# RomeBoardV1.net
KiCad netlist of a schematic drawn in EAGLE
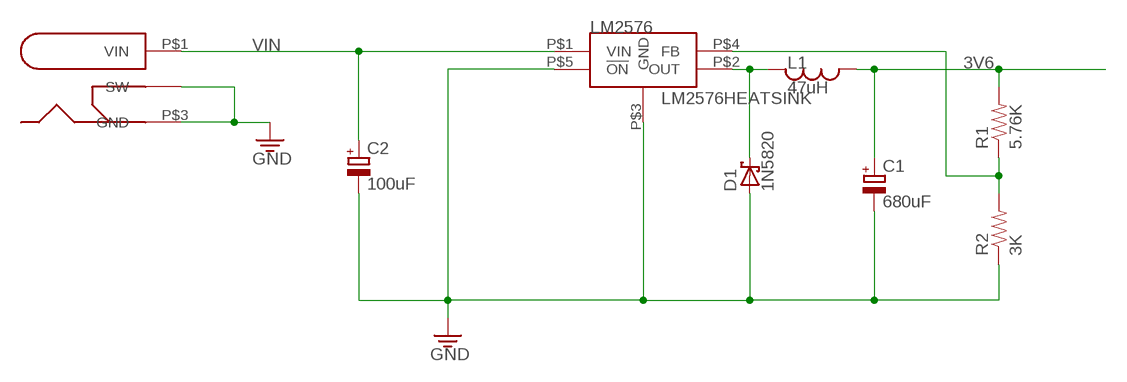
[diagram p0: schematic, sheet 1]
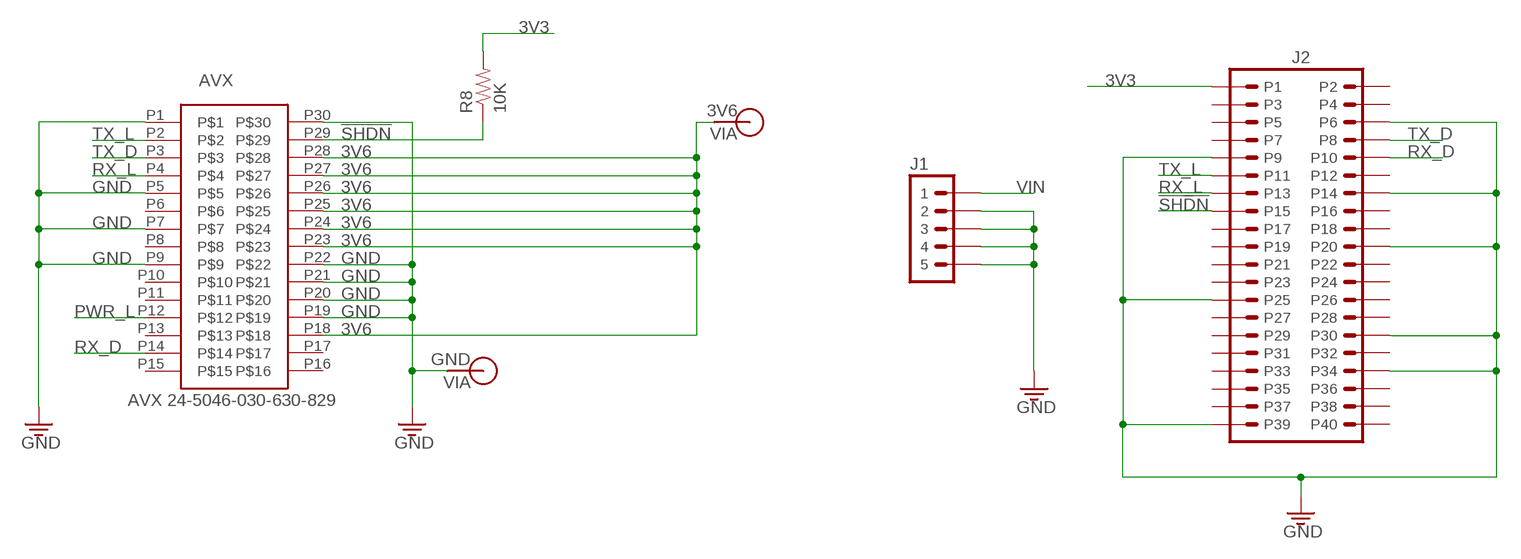
[diagram p1: schematic, sheet 2]
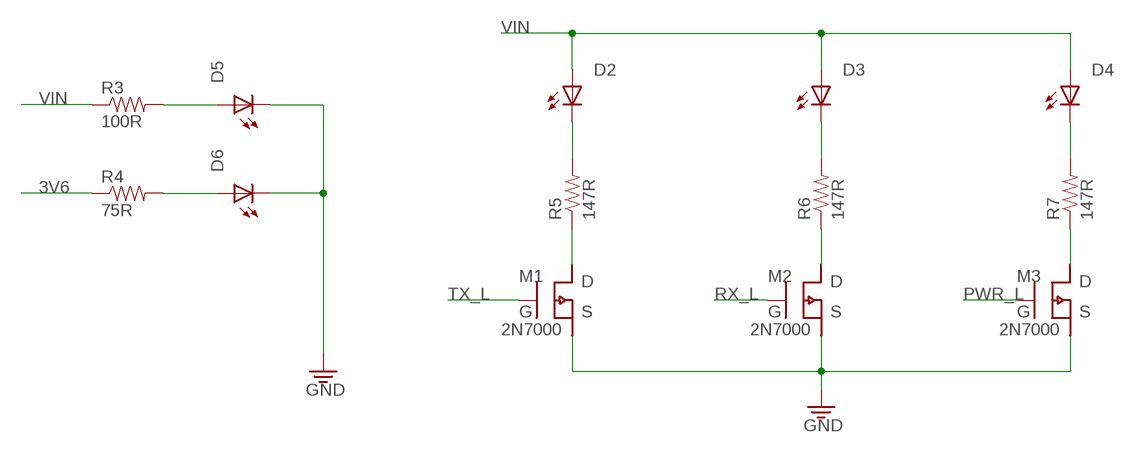
[diagram p2: schematic, sheet 3]

(export (version "E")
  (design (tool "Eeschema 10.0.6"))
  (components
    (comp (ref "AVX")
      (value "AVX-24-5046-030-630-829")
      (footprint "eagle-import:AVX-24-5046-630-829")
      (libsource (lib "eagle-import") (part "AVX-24-5046-030-630-829"))
    )
    (comp (ref "J1")
      (value "HEADER-5")
      (footprint "eagle-import:HEADER-05")
      (libsource (lib "eagle-import") (part "HEADER-5"))
    )
    (comp (ref "J2")
      (value "RASPBERRY-PI-HEADER")
      (footprint "eagle-import:HEADER-20X02")
      (libsource (lib "eagle-import") (part "RASPBERRY-PI-HEADER"))
    )
    (comp (ref "R8")
      (value "10K")
      (footprint "eagle-import:AXIAL-0.4")
      (libsource (lib "eagle-import") (part "RESISTOR-PTH0.4"))
    )
    (comp (ref "V4")
      (value "GND")
      (footprint "eagle-import:VIA-120MIL")
      (libsource (lib "eagle-import") (part "VIA-120MIL"))
    )
    (comp (ref "V5")
      (value "3V6")
      (footprint "eagle-import:VIA-120MIL")
      (libsource (lib "eagle-import") (part "VIA-120MIL"))
    )
    (comp (ref "C1")
      (value "680uF")
      (footprint "eagle-import:E5-10,5")
      (libsource (lib "eagle-import") (part "CPOL-EUE5-10.5"))
    )
    (comp (ref "C2")
      (value "100uF")
      (footprint "eagle-import:E3,5-10")
      (libsource (lib "eagle-import") (part "CPOL-EUE3.5-10"))
    )
    (comp (ref "D1")
      (value "1N5820")
      (footprint "eagle-import:DO-201AD")
      (libsource (lib "eagle-import") (part "1N5820"))
    )
    (comp (ref "L1")
      (value "47uH")
      (footprint "eagle-import:PE-53112NL")
      (libsource (lib "eagle-import") (part "INDPE-53112NL"))
    )
    (comp (ref "LM2576")
      (value "LM2576HEATSINK")
      (footprint "eagle-import:TO-220-5-HEATSINK")
      (libsource (lib "eagle-import") (part "LM2576HEATSINK"))
    )
    (comp (ref "R1")
      (value "5.76K")
      (footprint "eagle-import:AXIAL-0.4")
      (libsource (lib "eagle-import") (part "RESISTOR-PTH0.4"))
    )
    (comp (ref "R2")
      (value "3K")
      (footprint "eagle-import:AXIAL-0.4")
      (libsource (lib "eagle-import") (part "RESISTOR-PTH0.4"))
    )
    (comp (ref "U$2")
      (value "PJ-002A")
      (footprint "eagle-import:PJ-002A")
      (libsource (lib "eagle-import") (part "PJ-002A"))
    )
    (comp (ref "D2")
      (value "LEDTHRU-HOLE-CONNECTOR")
      (footprint "eagle-import:1X2-POL")
      (libsource (lib "eagle-import") (part "LEDTHRU-HOLE-CONNECTOR"))
    )
    (comp (ref "D3")
      (value "LEDTHRU-HOLE-CONNECTOR")
      (footprint "eagle-import:1X2-POL")
      (libsource (lib "eagle-import") (part "LEDTHRU-HOLE-CONNECTOR"))
    )
    (comp (ref "D4")
      (value "LEDTHRU-HOLE-CONNECTOR")
      (footprint "eagle-import:1X2-POL")
      (libsource (lib "eagle-import") (part "LEDTHRU-HOLE-CONNECTOR"))
    )
    (comp (ref "D5")
      (value "LEDTHRU-HOLE-CONNECTOR")
      (footprint "eagle-import:1X2-POL")
      (libsource (lib "eagle-import") (part "LEDTHRU-HOLE-CONNECTOR"))
    )
    (comp (ref "D6")
      (value "LEDTHRU-HOLE-CONNECTOR")
      (footprint "eagle-import:1X2-POL")
      (libsource (lib "eagle-import") (part "LEDTHRU-HOLE-CONNECTOR"))
    )
    (comp (ref "M1")
      (value "2N7000")
      (footprint "eagle-import:TO-923-MOS")
      (libsource (lib "eagle-import") (part "2N7000"))
    )
    (comp (ref "M2")
      (value "2N7000")
      (footprint "eagle-import:TO-923-MOS")
      (libsource (lib "eagle-import") (part "2N7000"))
    )
    (comp (ref "M3")
      (value "2N7000")
      (footprint "eagle-import:TO-923-MOS")
      (libsource (lib "eagle-import") (part "2N7000"))
    )
    (comp (ref "R3")
      (value "100R")
      (footprint "eagle-import:AXIAL-0.4")
      (libsource (lib "eagle-import") (part "RESISTOR-PTH0.4"))
    )
    (comp (ref "R4")
      (value "75R")
      (footprint "eagle-import:AXIAL-0.4")
      (libsource (lib "eagle-import") (part "RESISTOR-PTH0.4"))
    )
    (comp (ref "R5")
      (value "147R")
      (footprint "eagle-import:AXIAL-0.4")
      (libsource (lib "eagle-import") (part "RESISTOR-PTH0.4"))
    )
    (comp (ref "R6")
      (value "147R")
      (footprint "eagle-import:AXIAL-0.4")
      (libsource (lib "eagle-import") (part "RESISTOR-PTH0.4"))
    )
    (comp (ref "R7")
      (value "147R")
      (footprint "eagle-import:AXIAL-0.4")
      (libsource (lib "eagle-import") (part "RESISTOR-PTH0.4"))
    )
  )
  (nets
    (net (code "1") (name "3V3") (class "Default")
      (node (ref "J2") (pin "P1") (pinfunction "P1_P1") (pintype "passive"))
      (node (ref "R8") (pin "2") (pinfunction "2_2") (pintype "passive"))
    )
    (net (code "2") (name "3V6") (class "Default")
      (node (ref "AVX") (pin "P18") (pinfunction "P$18_P18") (pintype "bidirectional"))
      (node (ref "AVX") (pin "P23") (pinfunction "P$23_P23") (pintype "bidirectional"))
      (node (ref "AVX") (pin "P24") (pinfunction "P$24_P24") (pintype "bidirectional"))
      (node (ref "AVX") (pin "P25") (pinfunction "P$25_P25") (pintype "bidirectional"))
      (node (ref "AVX") (pin "P26") (pinfunction "P$26_P26") (pintype "bidirectional"))
      (node (ref "AVX") (pin "P27") (pinfunction "P$27_P27") (pintype "bidirectional"))
      (node (ref "AVX") (pin "P28") (pinfunction "P$28_P28") (pintype "bidirectional"))
      (node (ref "C1") (pin "+") (pinfunction "+_+") (pintype "passive"))
      (node (ref "L1") (pin "P$2") (pinfunction "P$2_P$2") (pintype "passive"))
      (node (ref "R1") (pin "2") (pinfunction "2_2") (pintype "passive"))
      (node (ref "R4") (pin "1") (pinfunction "1_1") (pintype "passive"))
      (node (ref "V5") (pin "P$1") (pinfunction "P$1_P$1") (pintype "bidirectional"))
    )
    (net (code "3") (name "GND") (class "Default")
      (node (ref "AVX") (pin "P1") (pinfunction "P$1_P1") (pintype "bidirectional"))
      (node (ref "AVX") (pin "P19") (pinfunction "P$19_P19") (pintype "bidirectional"))
      (node (ref "AVX") (pin "P20") (pinfunction "P$20_P20") (pintype "bidirectional"))
      (node (ref "AVX") (pin "P21") (pinfunction "P$21_P21") (pintype "bidirectional"))
      (node (ref "AVX") (pin "P22") (pinfunction "P$22_P22") (pintype "bidirectional"))
      (node (ref "AVX") (pin "P30") (pinfunction "P$30_P30") (pintype "bidirectional"))
      (node (ref "AVX") (pin "P5") (pinfunction "P$5_P5") (pintype "bidirectional"))
      (node (ref "AVX") (pin "P7") (pinfunction "P$7_P7") (pintype "bidirectional"))
      (node (ref "AVX") (pin "P9") (pinfunction "P$9_P9") (pintype "bidirectional"))
      (node (ref "C1") (pin "-") (pinfunction "-_-") (pintype "passive"))
      (node (ref "C2") (pin "-") (pinfunction "-_-") (pintype "passive"))
      (node (ref "D1") (pin "P$1") (pinfunction "A_P$1") (pintype "passive"))
      (node (ref "D5") (pin "2") (pinfunction "C_2") (pintype "passive"))
      (node (ref "D6") (pin "2") (pinfunction "C_2") (pintype "passive"))
      (node (ref "J1") (pin "2") (pinfunction "2_2") (pintype "passive"))
      (node (ref "J1") (pin "3") (pinfunction "3_3") (pintype "passive"))
      (node (ref "J1") (pin "4") (pinfunction "4_4") (pintype "passive"))
      (node (ref "J1") (pin "5") (pinfunction "5_5") (pintype "passive"))
      (node (ref "J2") (pin "P14") (pinfunction "P14_P14") (pintype "passive"))
      (node (ref "J2") (pin "P20") (pinfunction "P20_P20") (pintype "passive"))
      (node (ref "J2") (pin "P25") (pinfunction "P25_P25") (pintype "passive"))
      (node (ref "J2") (pin "P30") (pinfunction "P30_P30") (pintype "passive"))
      (node (ref "J2") (pin "P34") (pinfunction "P34_P34") (pintype "passive"))
      (node (ref "J2") (pin "P39") (pinfunction "P39_P39") (pintype "passive"))
      (node (ref "J2") (pin "P6") (pinfunction "P6_P6") (pintype "passive"))
      (node (ref "J2") (pin "P9") (pinfunction "P9_P9") (pintype "passive"))
      (node (ref "LM2576") (pin "P$3") (pinfunction "GND_P$3") (pintype "bidirectional"))
      (node (ref "LM2576") (pin "P$5") (pinfunction "~{ON}_P$5") (pintype "bidirectional"))
      (node (ref "M1") (pin "3") (pinfunction "S_3") (pintype "bidirectional"))
      (node (ref "M2") (pin "3") (pinfunction "S_3") (pintype "bidirectional"))
      (node (ref "M3") (pin "3") (pinfunction "S_3") (pintype "bidirectional"))
      (node (ref "R2") (pin "1") (pinfunction "1_1") (pintype "passive"))
      (node (ref "U$2") (pin "P$2") (pinfunction "SW_P$2") (pintype "bidirectional"))
      (node (ref "U$2") (pin "P$3") (pinfunction "GND_P$3") (pintype "bidirectional"))
      (node (ref "V4") (pin "P$1") (pinfunction "P$1_P$1") (pintype "bidirectional"))
    )
    (net (code "4") (name "Net-(D1-C)") (class "Default")
      (node (ref "D1") (pin "P$2") (pinfunction "C_P$2") (pintype "passive"))
      (node (ref "L1") (pin "P$1") (pinfunction "P$1_P$1") (pintype "passive"))
      (node (ref "LM2576") (pin "P$2") (pinfunction "OUT_P$2") (pintype "bidirectional"))
    )
    (net (code "5") (name "Net-(D2-C)") (class "Default")
      (node (ref "D2") (pin "2") (pinfunction "C_2") (pintype "passive"))
      (node (ref "R5") (pin "2") (pinfunction "2_2") (pintype "passive"))
    )
    (net (code "6") (name "Net-(D3-C)") (class "Default")
      (node (ref "D3") (pin "2") (pinfunction "C_2") (pintype "passive"))
      (node (ref "R6") (pin "2") (pinfunction "2_2") (pintype "passive"))
    )
    (net (code "7") (name "Net-(D4-C)") (class "Default")
      (node (ref "D4") (pin "2") (pinfunction "C_2") (pintype "passive"))
      (node (ref "R7") (pin "2") (pinfunction "2_2") (pintype "passive"))
    )
    (net (code "8") (name "Net-(D5-A)") (class "Default")
      (node (ref "D5") (pin "1") (pinfunction "A_1") (pintype "passive"))
      (node (ref "R3") (pin "2") (pinfunction "2_2") (pintype "passive"))
    )
    (net (code "9") (name "Net-(D6-A)") (class "Default")
      (node (ref "D6") (pin "1") (pinfunction "A_1") (pintype "passive"))
      (node (ref "R4") (pin "2") (pinfunction "2_2") (pintype "passive"))
    )
    (net (code "10") (name "Net-(LM2576-FB)") (class "Default")
      (node (ref "LM2576") (pin "P$4") (pinfunction "FB_P$4") (pintype "bidirectional"))
      (node (ref "R1") (pin "1") (pinfunction "1_1") (pintype "passive"))
      (node (ref "R2") (pin "2") (pinfunction "2_2") (pintype "passive"))
    )
    (net (code "11") (name "Net-(M1-D)") (class "Default")
      (node (ref "M1") (pin "1") (pinfunction "D_1") (pintype "bidirectional"))
      (node (ref "R5") (pin "1") (pinfunction "1_1") (pintype "passive"))
    )
    (net (code "12") (name "Net-(M2-D)") (class "Default")
      (node (ref "M2") (pin "1") (pinfunction "D_1") (pintype "bidirectional"))
      (node (ref "R6") (pin "1") (pinfunction "1_1") (pintype "passive"))
    )
    (net (code "13") (name "Net-(M3-D)") (class "Default")
      (node (ref "M3") (pin "1") (pinfunction "D_1") (pintype "bidirectional"))
      (node (ref "R7") (pin "1") (pinfunction "1_1") (pintype "passive"))
    )
    (net (code "14") (name "PWR_L") (class "Default")
      (node (ref "AVX") (pin "P12") (pinfunction "P$12_P12") (pintype "bidirectional"))
      (node (ref "M3") (pin "2") (pinfunction "G_2") (pintype "bidirectional"))
    )
    (net (code "15") (name "RX_D") (class "Default")
      (node (ref "AVX") (pin "P14") (pinfunction "P$14_P14") (pintype "bidirectional"))
      (node (ref "J2") (pin "P10") (pinfunction "P10_P10") (pintype "passive"))
    )
    (net (code "16") (name "RX_L") (class "Default")
      (node (ref "AVX") (pin "P4") (pinfunction "P$4_P4") (pintype "bidirectional"))
      (node (ref "J2") (pin "P13") (pinfunction "P13_P13") (pintype "passive"))
      (node (ref "M2") (pin "2") (pinfunction "G_2") (pintype "bidirectional"))
    )
    (net (code "17") (name "TX_D") (class "Default")
      (node (ref "AVX") (pin "P3") (pinfunction "P$3_P3") (pintype "bidirectional"))
      (node (ref "J2") (pin "P8") (pinfunction "P8_P8") (pintype "passive"))
    )
    (net (code "18") (name "TX_L") (class "Default")
      (node (ref "AVX") (pin "P2") (pinfunction "P$2_P2") (pintype "bidirectional"))
      (node (ref "J2") (pin "P11") (pinfunction "P11_P11") (pintype "passive"))
      (node (ref "M1") (pin "2") (pinfunction "G_2") (pintype "bidirectional"))
    )
    (net (code "19") (name "VIN") (class "Default")
      (node (ref "C2") (pin "+") (pinfunction "+_+") (pintype "passive"))
      (node (ref "D2") (pin "1") (pinfunction "A_1") (pintype "passive"))
      (node (ref "D3") (pin "1") (pinfunction "A_1") (pintype "passive"))
      (node (ref "D4") (pin "1") (pinfunction "A_1") (pintype "passive"))
      (node (ref "J1") (pin "1") (pinfunction "1_1") (pintype "passive"))
      (node (ref "LM2576") (pin "P$1") (pinfunction "VIN_P$1") (pintype "bidirectional"))
      (node (ref "R3") (pin "1") (pinfunction "1_1") (pintype "passive"))
      (node (ref "U$2") (pin "P$1") (pinfunction "VIN_P$1") (pintype "bidirectional"))
    )
    (net (code "20") (name "unconnected-(AVX-P$6-PadP6)") (class "Default")
      (node (ref "AVX") (pin "P6") (pinfunction "P$6_P6") (pintype "bidirectional"))
    )
    (net (code "21") (name "unconnected-(AVX-P$8-PadP8)") (class "Default")
      (node (ref "AVX") (pin "P8") (pinfunction "P$8_P8") (pintype "bidirectional"))
    )
    (net (code "22") (name "unconnected-(AVX-P$10-PadP10)") (class "Default")
      (node (ref "AVX") (pin "P10") (pinfunction "P$10_P10") (pintype "bidirectional"))
    )
    (net (code "23") (name "unconnected-(AVX-P$11-PadP11)") (class "Default")
      (node (ref "AVX") (pin "P11") (pinfunction "P$11_P11") (pintype "bidirectional"))
    )
    (net (code "24") (name "unconnected-(AVX-P$13-PadP13)") (class "Default")
      (node (ref "AVX") (pin "P13") (pinfunction "P$13_P13") (pintype "bidirectional"))
    )
    (net (code "25") (name "unconnected-(AVX-P$15-PadP15)") (class "Default")
      (node (ref "AVX") (pin "P15") (pinfunction "P$15_P15") (pintype "bidirectional"))
    )
    (net (code "26") (name "unconnected-(AVX-P$16-PadP16)") (class "Default")
      (node (ref "AVX") (pin "P16") (pinfunction "P$16_P16") (pintype "bidirectional"))
    )
    (net (code "27") (name "unconnected-(AVX-P$17-PadP17)") (class "Default")
      (node (ref "AVX") (pin "P17") (pinfunction "P$17_P17") (pintype "bidirectional"))
    )
    (net (code "28") (name "unconnected-(J2-PadP2)") (class "Default")
      (node (ref "J2") (pin "P2") (pinfunction "P2_P2") (pintype "passive"))
    )
    (net (code "29") (name "unconnected-(J2-PadP3)") (class "Default")
      (node (ref "J2") (pin "P3") (pinfunction "P3_P3") (pintype "passive"))
    )
    (net (code "30") (name "unconnected-(J2-PadP4)") (class "Default")
      (node (ref "J2") (pin "P4") (pinfunction "P4_P4") (pintype "passive"))
    )
    (net (code "31") (name "unconnected-(J2-PadP5)") (class "Default")
      (node (ref "J2") (pin "P5") (pinfunction "P5_P5") (pintype "passive"))
    )
    (net (code "32") (name "unconnected-(J2-PadP7)") (class "Default")
      (node (ref "J2") (pin "P7") (pinfunction "P7_P7") (pintype "passive"))
    )
    (net (code "33") (name "unconnected-(J2-PadP12)") (class "Default")
      (node (ref "J2") (pin "P12") (pinfunction "P12_P12") (pintype "passive"))
    )
    (net (code "34") (name "unconnected-(J2-PadP16)") (class "Default")
      (node (ref "J2") (pin "P16") (pinfunction "P16_P16") (pintype "passive"))
    )
    (net (code "35") (name "unconnected-(J2-PadP17)") (class "Default")
      (node (ref "J2") (pin "P17") (pinfunction "P17_P17") (pintype "passive"))
    )
    (net (code "36") (name "unconnected-(J2-PadP18)") (class "Default")
      (node (ref "J2") (pin "P18") (pinfunction "P18_P18") (pintype "passive"))
    )
    (net (code "37") (name "unconnected-(J2-PadP19)") (class "Default")
      (node (ref "J2") (pin "P19") (pinfunction "P19_P19") (pintype "passive"))
    )
    (net (code "38") (name "unconnected-(J2-PadP21)") (class "Default")
      (node (ref "J2") (pin "P21") (pinfunction "P21_P21") (pintype "passive"))
    )
    (net (code "39") (name "unconnected-(J2-PadP22)") (class "Default")
      (node (ref "J2") (pin "P22") (pinfunction "P22_P22") (pintype "passive"))
    )
    (net (code "40") (name "unconnected-(J2-PadP23)") (class "Default")
      (node (ref "J2") (pin "P23") (pinfunction "P23_P23") (pintype "passive"))
    )
    (net (code "41") (name "unconnected-(J2-PadP24)") (class "Default")
      (node (ref "J2") (pin "P24") (pinfunction "P24_P24") (pintype "passive"))
    )
    (net (code "42") (name "unconnected-(J2-PadP26)") (class "Default")
      (node (ref "J2") (pin "P26") (pinfunction "P26_P26") (pintype "passive"))
    )
    (net (code "43") (name "unconnected-(J2-PadP27)") (class "Default")
      (node (ref "J2") (pin "P27") (pinfunction "P27_P27") (pintype "passive"))
    )
    (net (code "44") (name "unconnected-(J2-PadP28)") (class "Default")
      (node (ref "J2") (pin "P28") (pinfunction "P28_P28") (pintype "passive"))
    )
    (net (code "45") (name "unconnected-(J2-PadP29)") (class "Default")
      (node (ref "J2") (pin "P29") (pinfunction "P29_P29") (pintype "passive"))
    )
    (net (code "46") (name "unconnected-(J2-PadP31)") (class "Default")
      (node (ref "J2") (pin "P31") (pinfunction "P31_P31") (pintype "passive"))
    )
    (net (code "47") (name "unconnected-(J2-PadP32)") (class "Default")
      (node (ref "J2") (pin "P32") (pinfunction "P32_P32") (pintype "passive"))
    )
    (net (code "48") (name "unconnected-(J2-PadP33)") (class "Default")
      (node (ref "J2") (pin "P33") (pinfunction "P33_P33") (pintype "passive"))
    )
    (net (code "49") (name "unconnected-(J2-PadP35)") (class "Default")
      (node (ref "J2") (pin "P35") (pinfunction "P35_P35") (pintype "passive"))
    )
    (net (code "50") (name "unconnected-(J2-PadP36)") (class "Default")
      (node (ref "J2") (pin "P36") (pinfunction "P36_P36") (pintype "passive"))
    )
    (net (code "51") (name "unconnected-(J2-PadP37)") (class "Default")
      (node (ref "J2") (pin "P37") (pinfunction "P37_P37") (pintype "passive"))
    )
    (net (code "52") (name "unconnected-(J2-PadP38)") (class "Default")
      (node (ref "J2") (pin "P38") (pinfunction "P38_P38") (pintype "passive"))
    )
    (net (code "53") (name "unconnected-(J2-PadP40)") (class "Default")
      (node (ref "J2") (pin "P40") (pinfunction "P40_P40") (pintype "passive"))
    )
    (net (code "54") (name "~{SHDN}") (class "Default")
      (node (ref "AVX") (pin "P29") (pinfunction "P$29_P29") (pintype "bidirectional"))
      (node (ref "J2") (pin "P15") (pinfunction "P15_P15") (pintype "passive"))
      (node (ref "R8") (pin "1") (pinfunction "1_1") (pintype "passive"))
    )
  )
)
